# Fan.net
KiCad netlist of a schematic drawn in Altium Designer
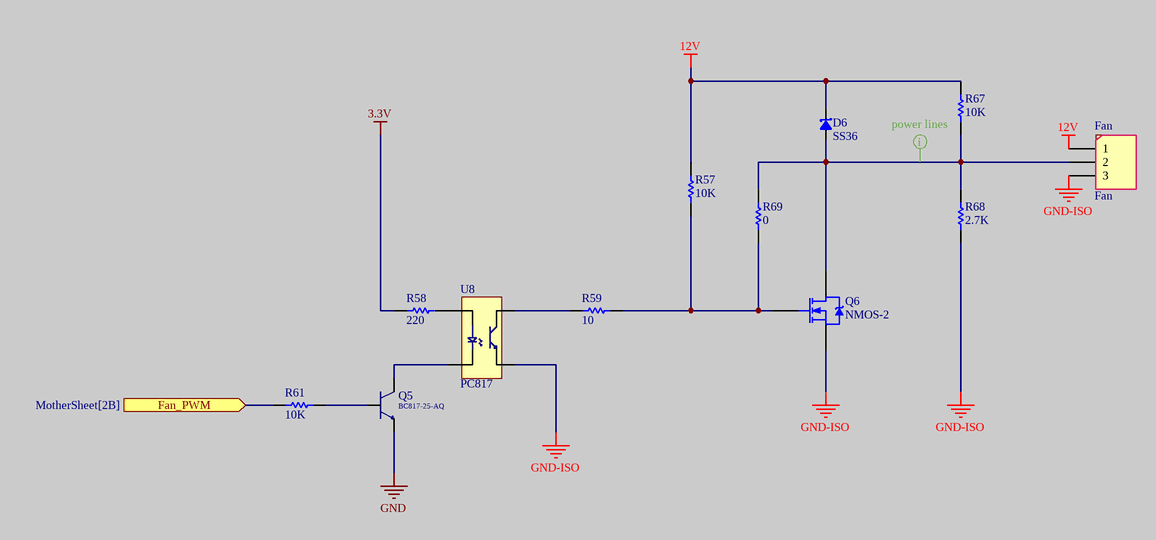
[diagram p0: Fan.SchDoc]

(export (version "E")
  (design (tool "Eeschema 10.0.6"))
  (components
    (comp (ref "D6")
      (value "SS36")
      (footprint "SMA")
      (description "Fast Schottky Diode")
      (fields (field (name "PUBLISHER") "Altium Limited"))
      (libsource (lib "eLIB") (part "SS36"))
    )
    (comp (ref "Fan")
      (value "Fan")
      (footprint "HEADER1*3")
      (description "Header, 3-Pin")
      (fields (field (name "PUBLISHER") "Altium Limited"))
      (libsource (lib "eLIB") (part "Header1*3"))
    )
    (comp (ref "Q5")
      (value "NPN transistor")
      (footprint "NPN")
      (description "45 V, 0.5 A")
      (fields (field (name "TRANSISTOR") "BC817-25-AQ"))
      (libsource (lib "eLIB") (part "BC817"))
    )
    (comp (ref "Q6")
      (value "NMOS-2")
      (footprint "dpak")
      (description "N-Channel Power MOSFET")
      (fields (field (name "PUBLISHER") "Altium Limited"))
      (libsource (lib "eLIB") (part "NMOS-2"))
    )
    (comp (ref "R57")
      (value "10K")
      (footprint "RESC0603")
      (description "0603,0.1W")
      (fields (field (name "PUBLISHER") "Altium Limited"))
      (libsource (lib "eLIB") (part "Resistor"))
    )
    (comp (ref "R58")
      (value "220")
      (footprint "RESC0603")
      (description "0603,0.1W")
      (fields (field (name "PUBLISHER") "Altium Limited"))
      (libsource (lib "eLIB") (part "Resistor"))
    )
    (comp (ref "R59")
      (value "10")
      (footprint "RESC0603")
      (description "0603,0.1W")
      (fields (field (name "PUBLISHER") "Altium Limited"))
      (libsource (lib "eLIB") (part "Resistor"))
    )
    (comp (ref "R61")
      (value "10K")
      (footprint "RESC0603")
      (description "0603,0.1W")
      (fields (field (name "PUBLISHER") "Altium Limited"))
      (libsource (lib "eLIB") (part "Resistor"))
    )
    (comp (ref "R67")
      (value "10K")
      (footprint "RESC0603")
      (description "0603,0.1W")
      (fields (field (name "PUBLISHER") "Altium Limited"))
      (libsource (lib "eLIB") (part "Resistor"))
    )
    (comp (ref "R68")
      (value "2.7K")
      (footprint "RESC0603")
      (description "0603,0.1W")
      (fields (field (name "PUBLISHER") "Altium Limited"))
      (libsource (lib "eLIB") (part "Resistor"))
    )
    (comp (ref "R69")
      (value "0")
      (footprint "RESC0603")
      (description "0603,0.1W")
      (fields (field (name "PUBLISHER") "Altium Limited"))
      (libsource (lib "eLIB") (part "Resistor"))
    )
    (comp (ref "U8")
      (value "PC817")
      (footprint "PC817")
      (description "PC817 optocoupler")
      (libsource (lib "eLIB") (part "PC817"))
    )
  )
  (nets
    (net (code "1") (name "/Fan_PWM") (class "Default")
      (node (ref "R61") (pin "2") (pinfunction "2_2") (pintype "passive"))
    )
    (net (code "2") (name "3.3V") (class "Default")
      (node (ref "R58") (pin "2") (pinfunction "2_2") (pintype "passive"))
    )
    (net (code "3") (name "12V") (class "Default")
      (node (ref "D6") (pin "2") (pinfunction "K_2") (pintype "passive"))
      (node (ref "Fan") (pin "1") (pinfunction "1_1") (pintype "passive"))
      (node (ref "R57") (pin "1") (pinfunction "1_1") (pintype "passive"))
      (node (ref "R67") (pin "1") (pinfunction "1_1") (pintype "passive"))
    )
    (net (code "4") (name "GND") (class "Default")
      (node (ref "Q5") (pin "2") (pinfunction "E_2") (pintype "passive"))
    )
    (net (code "5") (name "GND-ISO") (class "Default")
      (node (ref "Fan") (pin "3") (pinfunction "3_3") (pintype "passive"))
      (node (ref "Q6") (pin "3") (pinfunction "S_3") (pintype "passive"))
      (node (ref "R68") (pin "2") (pinfunction "2_2") (pintype "passive"))
      (node (ref "U8") (pin "3") (pinfunction "3_3") (pintype "passive"))
    )
    (net (code "6") (name "Net-(D6-A)") (class "Default")
      (node (ref "D6") (pin "1") (pinfunction "A_1") (pintype "passive"))
      (node (ref "Fan") (pin "2") (pinfunction "2_2") (pintype "passive"))
      (node (ref "Q6") (pin "2") (pinfunction "D_2") (pintype "passive"))
      (node (ref "R67") (pin "2") (pinfunction "2_2") (pintype "passive"))
      (node (ref "R68") (pin "1") (pinfunction "1_1") (pintype "passive"))
      (node (ref "R69") (pin "1") (pinfunction "1_1") (pintype "passive"))
    )
    (net (code "7") (name "Net-(Q5-B)") (class "Default")
      (node (ref "Q5") (pin "1") (pinfunction "B_1") (pintype "passive"))
      (node (ref "R61") (pin "1") (pinfunction "1_1") (pintype "passive"))
    )
    (net (code "8") (name "Net-(Q5-C)") (class "Default")
      (node (ref "Q5") (pin "3") (pinfunction "C_3") (pintype "passive"))
      (node (ref "U8") (pin "2") (pinfunction "2_2") (pintype "passive"))
    )
    (net (code "9") (name "Net-(Q6-G)") (class "Default")
      (node (ref "Q6") (pin "1") (pinfunction "G_1") (pintype "passive"))
      (node (ref "R57") (pin "2") (pinfunction "2_2") (pintype "passive"))
      (node (ref "R59") (pin "2") (pinfunction "2_2") (pintype "passive"))
      (node (ref "R69") (pin "2") (pinfunction "2_2") (pintype "passive"))
    )
    (net (code "10") (name "Net-(R58-Pad1)") (class "Default")
      (node (ref "R58") (pin "1") (pinfunction "1_1") (pintype "passive"))
      (node (ref "U8") (pin "1") (pinfunction "1_1") (pintype "passive"))
    )
    (net (code "11") (name "Net-(R59-Pad1)") (class "Default")
      (node (ref "R59") (pin "1") (pinfunction "1_1") (pintype "passive"))
      (node (ref "U8") (pin "4") (pinfunction "4_4") (pintype "passive"))
    )
  )
)
